# ir_sensor.net
KiCad netlist of a schematic drawn in EAGLE
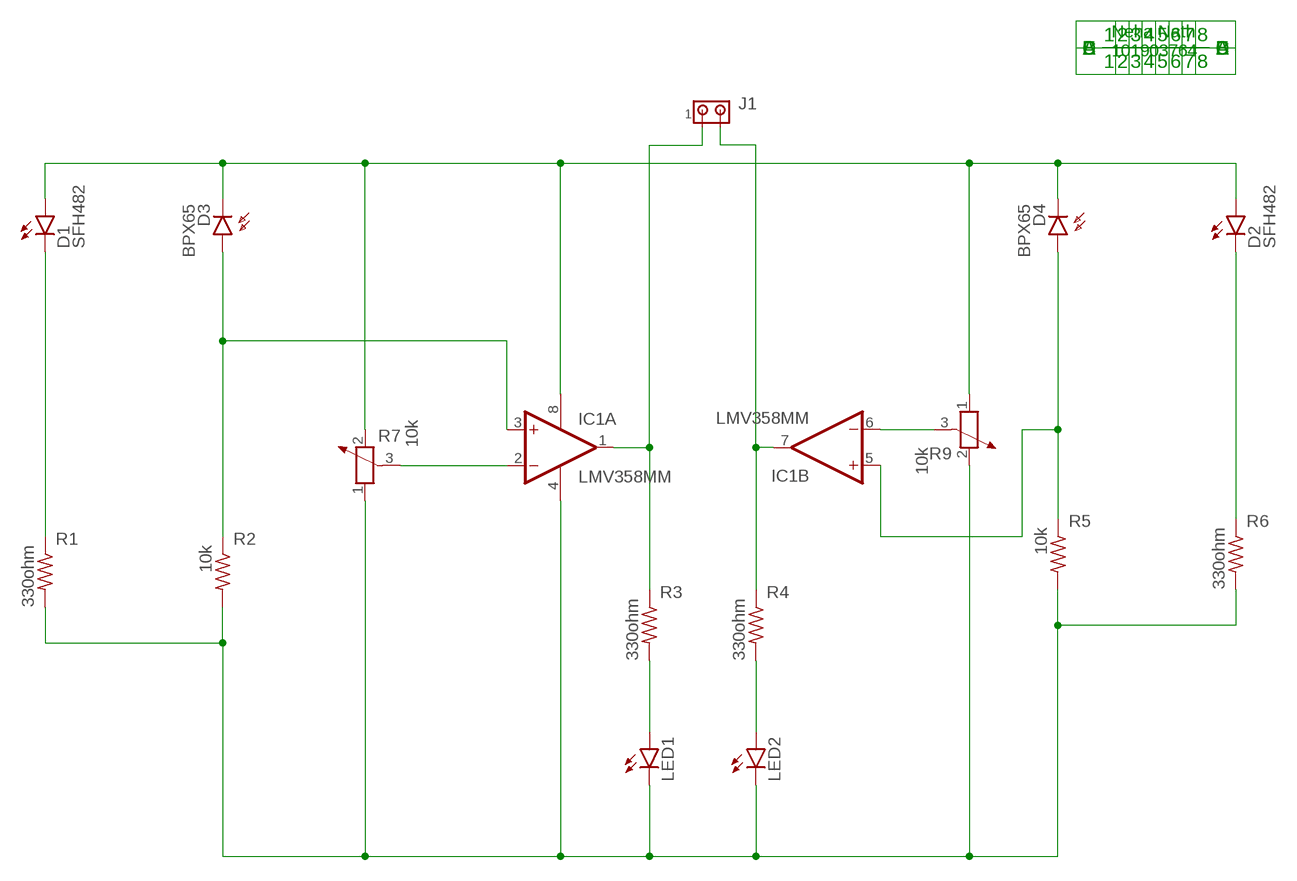
[diagram p0: schematic, sheet 1]

(export (version "E")
  (design (tool "Eeschema 10.0.6"))
  (components
    (comp (ref "D1")
      (value "SFH482")
      (footprint "eagle-import:SFH482")
      (libsource (lib "eagle-import") (part "SFH482"))
    )
    (comp (ref "D2")
      (value "SFH482")
      (footprint "eagle-import:SFH482")
      (libsource (lib "eagle-import") (part "SFH482"))
    )
    (comp (ref "D3")
      (value "BPX65")
      (footprint "eagle-import:BPX65")
      (fields (field (name "MPN") "BPX65."))
      (libsource (lib "eagle-import") (part "BPX65"))
    )
    (comp (ref "D4")
      (value "BPX65")
      (footprint "eagle-import:BPX65")
      (fields (field (name "MPN") "BPX65."))
      (libsource (lib "eagle-import") (part "BPX65"))
    )
    (comp (ref "IC1")
      (value "LMV358MM")
      (footprint "eagle-import:MSOP08")
      (libsource (lib "eagle-import") (part "LMV358?MM"))
    )
    (comp (ref "J1")
      (value "MTA02-100")
      (footprint "eagle-import:10X02MTA")
      (libsource (lib "eagle-import") (part "MTA02-100"))
    )
    (comp (ref "LED1")
      (value "LED3MM")
      (footprint "eagle-import:LED3MM")
      (libsource (lib "eagle-import") (part "LED3MM"))
    )
    (comp (ref "LED2")
      (value "LED3MM")
      (footprint "eagle-import:LED3MM")
      (libsource (lib "eagle-import") (part "LED3MM"))
    )
    (comp (ref "R1")
      (value "330ohm")
      (footprint "eagle-import:0207_10")
      (libsource (lib "eagle-import") (part "R-US_0207/10"))
    )
    (comp (ref "R2")
      (value "10k")
      (footprint "eagle-import:0207_10")
      (libsource (lib "eagle-import") (part "R-US_0207/10"))
    )
    (comp (ref "R3")
      (value "330ohm")
      (footprint "eagle-import:0207_10")
      (libsource (lib "eagle-import") (part "R-US_0207/10"))
    )
    (comp (ref "R4")
      (value "330ohm")
      (footprint "eagle-import:0207_10")
      (libsource (lib "eagle-import") (part "R-US_0207/10"))
    )
    (comp (ref "R5")
      (value "10k")
      (footprint "eagle-import:0207_10")
      (libsource (lib "eagle-import") (part "R-US_0207/10"))
    )
    (comp (ref "R6")
      (value "330ohm")
      (footprint "eagle-import:0207_10")
      (libsource (lib "eagle-import") (part "R-US_0207/10"))
    )
    (comp (ref "R7")
      (value "10k")
      (footprint "eagle-import:PT-10S")
      (libsource (lib "eagle-import") (part "POTENTIOMETER_PT-10S"))
    )
    (comp (ref "R9")
      (value "10k")
      (footprint "eagle-import:PT-10S")
      (libsource (lib "eagle-import") (part "POTENTIOMETER_PT-10S"))
    )
  )
  (nets
    (net (code "1") (name "Net-(D1-C)") (class "Default")
      (node (ref "D1") (pin "K") (pinfunction "C_K") (pintype "passive"))
      (node (ref "R1") (pin "1") (pinfunction "1_1") (pintype "passive"))
    )
    (net (code "2") (name "Net-(D2-C)") (class "Default")
      (node (ref "D2") (pin "K") (pinfunction "C_K") (pintype "passive"))
      (node (ref "R6") (pin "1") (pinfunction "1_1") (pintype "passive"))
    )
    (net (code "3") (name "Net-(D3-C)") (class "Default")
      (node (ref "D1") (pin "A") (pinfunction "A_A") (pintype "passive"))
      (node (ref "D2") (pin "A") (pinfunction "A_A") (pintype "passive"))
      (node (ref "D3") (pin "K") (pinfunction "C_K") (pintype "passive"))
      (node (ref "D4") (pin "K") (pinfunction "C_K") (pintype "passive"))
      (node (ref "IC1") (pin "8") (pinfunction "V+_8") (pintype "power_in"))
      (node (ref "R7") (pin "2") (pinfunction "2_2") (pintype "passive"))
      (node (ref "R9") (pin "1") (pinfunction "1_1") (pintype "passive"))
    )
    (net (code "4") (name "Net-(IC1A-+IN)") (class "Default")
      (node (ref "D3") (pin "A") (pinfunction "A_A") (pintype "passive"))
      (node (ref "IC1") (pin "3") (pinfunction "+IN_3") (pintype "input"))
      (node (ref "R2") (pin "1") (pinfunction "1_1") (pintype "passive"))
    )
    (net (code "5") (name "Net-(IC1A--IN)") (class "Default")
      (node (ref "IC1") (pin "2") (pinfunction "-IN_2") (pintype "input"))
      (node (ref "R7") (pin "3") (pinfunction "3_3") (pintype "passive"))
    )
    (net (code "6") (name "Net-(IC1A-OUT)") (class "Default")
      (node (ref "IC1") (pin "1") (pinfunction "OUT_1") (pintype "output"))
      (node (ref "J1") (pin "1") (pinfunction "1_1") (pintype "passive"))
      (node (ref "R3") (pin "1") (pinfunction "1_1") (pintype "passive"))
    )
    (net (code "7") (name "Net-(IC1B-+IN)") (class "Default")
      (node (ref "D4") (pin "A") (pinfunction "A_A") (pintype "passive"))
      (node (ref "IC1") (pin "5") (pinfunction "+IN_5") (pintype "input"))
      (node (ref "R5") (pin "1") (pinfunction "1_1") (pintype "passive"))
    )
    (net (code "8") (name "Net-(IC1B--IN)") (class "Default")
      (node (ref "IC1") (pin "6") (pinfunction "-IN_6") (pintype "input"))
      (node (ref "R9") (pin "3") (pinfunction "3_3") (pintype "passive"))
    )
    (net (code "9") (name "Net-(IC1B-OUT)") (class "Default")
      (node (ref "IC1") (pin "7") (pinfunction "OUT_7") (pintype "output"))
      (node (ref "J1") (pin "2") (pinfunction "2_2") (pintype "passive"))
      (node (ref "R4") (pin "1") (pinfunction "1_1") (pintype "passive"))
    )
    (net (code "10") (name "Net-(IC1C-V-)") (class "Default")
      (node (ref "IC1") (pin "4") (pinfunction "V-_4") (pintype "power_in"))
      (node (ref "LED1") (pin "K") (pinfunction "C_K") (pintype "passive"))
      (node (ref "LED2") (pin "K") (pinfunction "C_K") (pintype "passive"))
      (node (ref "R1") (pin "2") (pinfunction "2_2") (pintype "passive"))
      (node (ref "R2") (pin "2") (pinfunction "2_2") (pintype "passive"))
      (node (ref "R5") (pin "2") (pinfunction "2_2") (pintype "passive"))
      (node (ref "R6") (pin "2") (pinfunction "2_2") (pintype "passive"))
      (node (ref "R7") (pin "1") (pinfunction "1_1") (pintype "passive"))
      (node (ref "R9") (pin "2") (pinfunction "2_2") (pintype "passive"))
    )
    (net (code "11") (name "Net-(LED1-PadA)") (class "Default")
      (node (ref "LED1") (pin "A") (pinfunction "A_A") (pintype "passive"))
      (node (ref "R3") (pin "2") (pinfunction "2_2") (pintype "passive"))
    )
    (net (code "12") (name "Net-(LED2-PadA)") (class "Default")
      (node (ref "LED2") (pin "A") (pinfunction "A_A") (pintype "passive"))
      (node (ref "R4") (pin "2") (pinfunction "2_2") (pintype "passive"))
    )
  )
)
